# wavplayer-v2.net
KiCad netlist of a schematic drawn in EAGLE
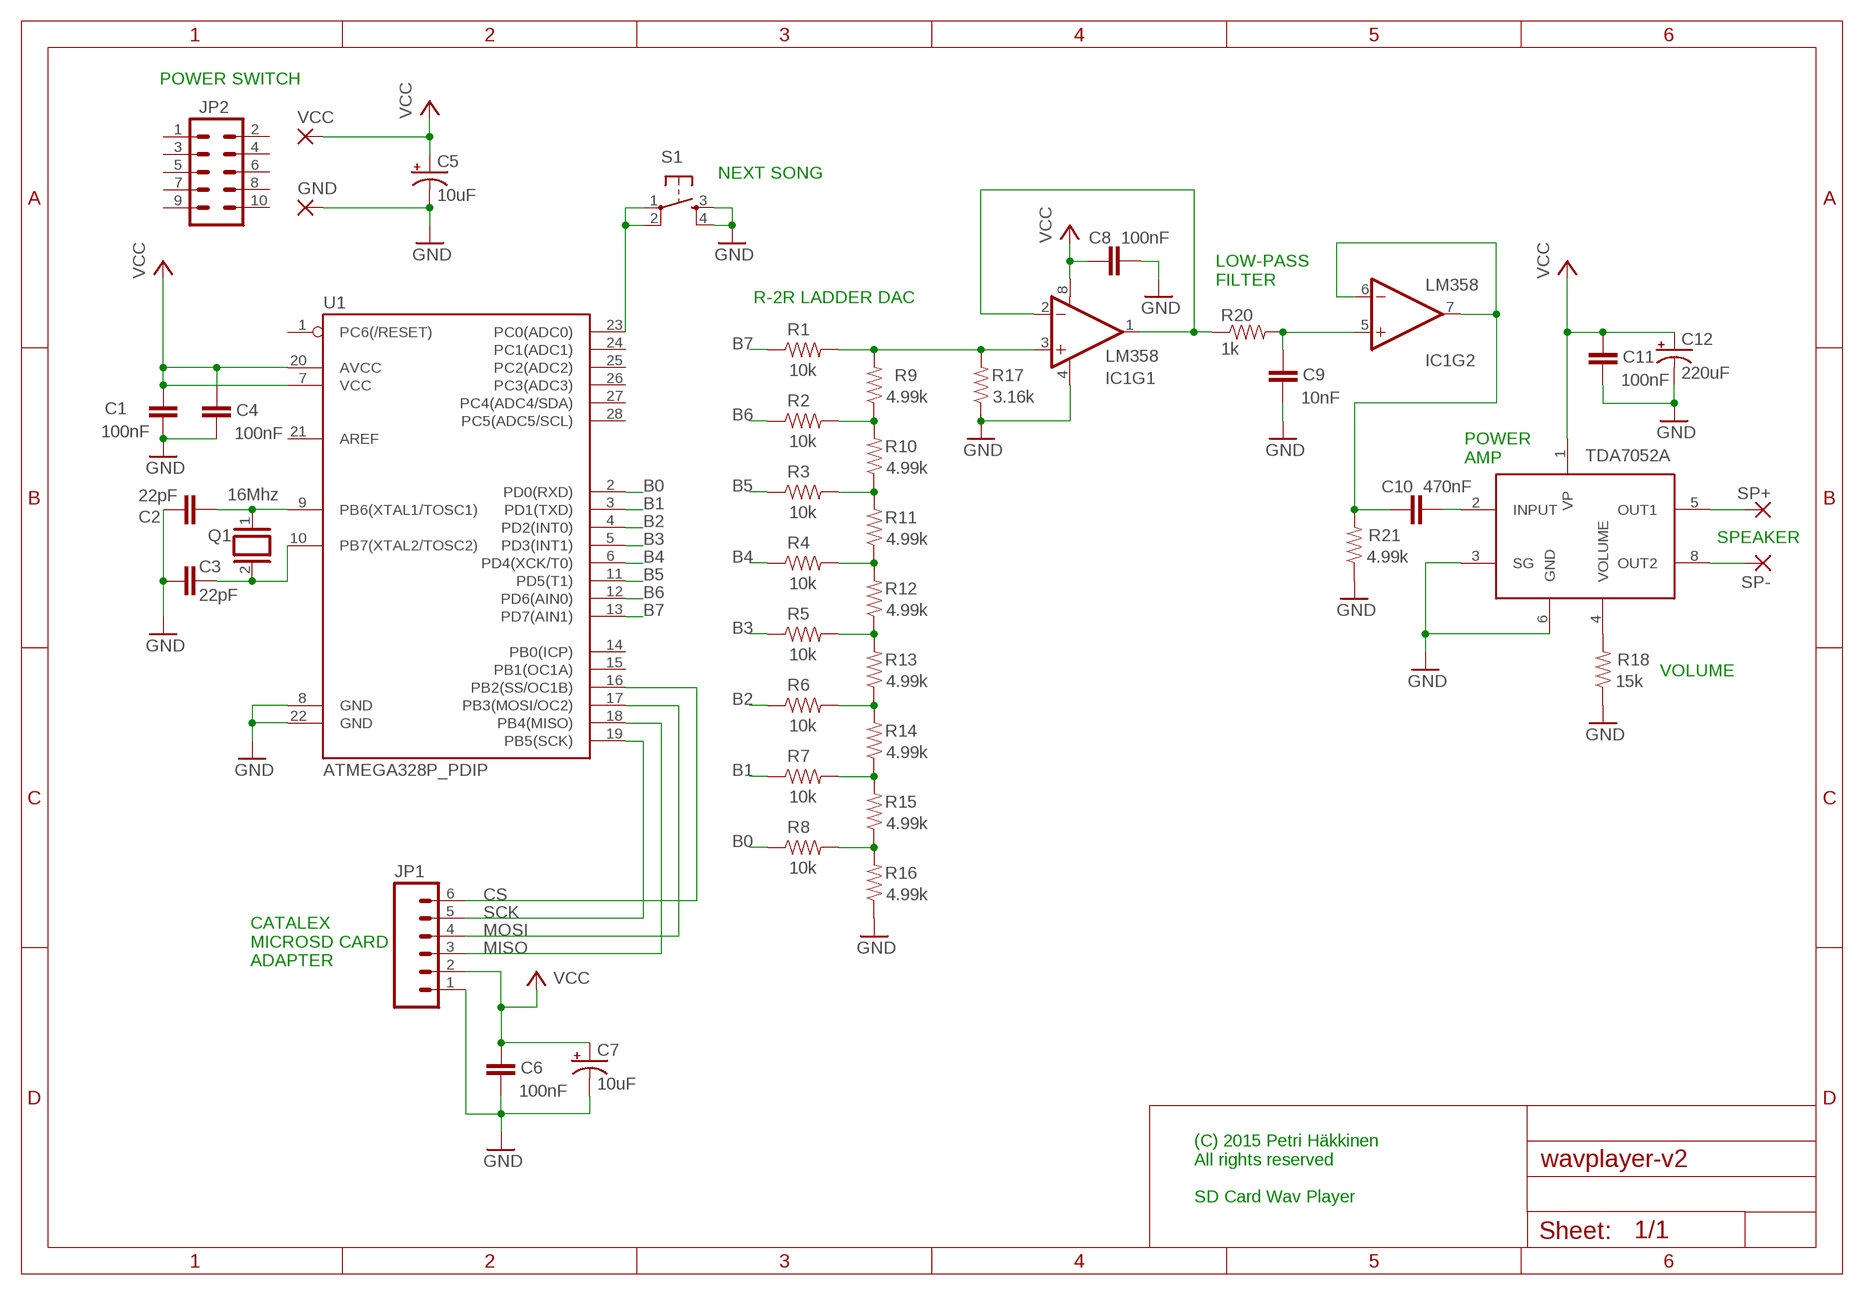
[diagram p0: schematic, sheet 1]

(export (version "E")
  (design (tool "Eeschema 10.0.6"))
  (components
    (comp (ref "C1")
      (value "100nF")
      (footprint "eagle-import:CAP-PTH-SMALL")
      (libsource (lib "eagle-import") (part "CAPPTH"))
    )
    (comp (ref "C2")
      (value "22pF")
      (footprint "eagle-import:CAP-PTH-SMALL")
      (libsource (lib "eagle-import") (part "CAPPTH"))
    )
    (comp (ref "C3")
      (value "22pF")
      (footprint "eagle-import:CAP-PTH-SMALL")
      (libsource (lib "eagle-import") (part "CAPPTH"))
    )
    (comp (ref "C4")
      (value "100nF")
      (footprint "eagle-import:CAP-PTH-SMALL")
      (libsource (lib "eagle-import") (part "CAPPTH"))
    )
    (comp (ref "C5")
      (value "10uF")
      (footprint "eagle-import:CPOL-RADIAL-100UF-25V")
      (libsource (lib "eagle-import") (part "CAP_POLPTH1"))
    )
    (comp (ref "C6")
      (value "100nF")
      (footprint "eagle-import:CAP-PTH-SMALL")
      (libsource (lib "eagle-import") (part "CAPPTH"))
    )
    (comp (ref "C7")
      (value "10uF")
      (footprint "eagle-import:CPOL-RADIAL-100UF-25V")
      (libsource (lib "eagle-import") (part "CAP_POLPTH1"))
    )
    (comp (ref "C8")
      (value "100nF")
      (footprint "eagle-import:CAP-PTH-SMALL")
      (libsource (lib "eagle-import") (part "CAPPTH"))
    )
    (comp (ref "C9")
      (value "10nF")
      (footprint "eagle-import:CAP-PTH-SMALL")
      (libsource (lib "eagle-import") (part "CAPPTH"))
    )
    (comp (ref "C10")
      (value "470nF")
      (footprint "eagle-import:CAP-PTH-SMALL")
      (libsource (lib "eagle-import") (part "CAPPTH"))
    )
    (comp (ref "C11")
      (value "100nF")
      (footprint "eagle-import:CAP-PTH-SMALL")
      (libsource (lib "eagle-import") (part "CAPPTH"))
    )
    (comp (ref "C12")
      (value "220uF")
      (footprint "eagle-import:CPOL-RADIAL-100UF-25V")
      (libsource (lib "eagle-import") (part "CAP_POLPTH1"))
    )
    (comp (ref "GND")
      (value "WIREPAD2,54/0,8")
      (footprint "eagle-import:2,54_0,8")
      (libsource (lib "eagle-import") (part "WIREPAD2,54/0,8"))
    )
    (comp (ref "IC1")
      (value "LM358")
      (footprint "eagle-import:DIP08")
      (libsource (lib "eagle-import") (part "LM358"))
    )
    (comp (ref "JP1")
      (value "M06LONGPADS")
      (footprint "eagle-import:1X06_LONGPADS")
      (libsource (lib "eagle-import") (part "M06LONGPADS"))
    )
    (comp (ref "JP2")
      (value "M05X2NO_SILK")
      (footprint "eagle-import:2X5_NOSILK")
      (libsource (lib "eagle-import") (part "M05X2NO_SILK"))
    )
    (comp (ref "Q1")
      (value "16Mhz")
      (footprint "eagle-import:QS")
      (libsource (lib "eagle-import") (part "XTAL/S"))
    )
    (comp (ref "R1")
      (value "10k")
      (footprint "eagle-import:AXIAL-0.4")
      (libsource (lib "eagle-import") (part "RESISTORPTH-1/4W"))
    )
    (comp (ref "R2")
      (value "10k")
      (footprint "eagle-import:AXIAL-0.4")
      (libsource (lib "eagle-import") (part "RESISTORPTH-1/4W"))
    )
    (comp (ref "R3")
      (value "10k")
      (footprint "eagle-import:AXIAL-0.4")
      (libsource (lib "eagle-import") (part "RESISTORPTH-1/4W"))
    )
    (comp (ref "R4")
      (value "10k")
      (footprint "eagle-import:AXIAL-0.4")
      (libsource (lib "eagle-import") (part "RESISTORPTH-1/4W"))
    )
    (comp (ref "R5")
      (value "10k")
      (footprint "eagle-import:AXIAL-0.4")
      (libsource (lib "eagle-import") (part "RESISTORPTH-1/4W"))
    )
    (comp (ref "R6")
      (value "10k")
      (footprint "eagle-import:AXIAL-0.4")
      (libsource (lib "eagle-import") (part "RESISTORPTH-1/4W"))
    )
    (comp (ref "R7")
      (value "10k")
      (footprint "eagle-import:AXIAL-0.4")
      (libsource (lib "eagle-import") (part "RESISTORPTH-1/4W"))
    )
    (comp (ref "R8")
      (value "10k")
      (footprint "eagle-import:AXIAL-0.4")
      (libsource (lib "eagle-import") (part "RESISTORPTH-1/4W"))
    )
    (comp (ref "R9")
      (value "4.99k")
      (footprint "eagle-import:AXIAL-0.4")
      (libsource (lib "eagle-import") (part "RESISTORPTH-1/4W"))
    )
    (comp (ref "R10")
      (value "4.99k")
      (footprint "eagle-import:AXIAL-0.4")
      (libsource (lib "eagle-import") (part "RESISTORPTH-1/4W"))
    )
    (comp (ref "R11")
      (value "4.99k")
      (footprint "eagle-import:AXIAL-0.4")
      (libsource (lib "eagle-import") (part "RESISTORPTH-1/4W"))
    )
    (comp (ref "R12")
      (value "4.99k")
      (footprint "eagle-import:AXIAL-0.4")
      (libsource (lib "eagle-import") (part "RESISTORPTH-1/4W"))
    )
    (comp (ref "R13")
      (value "4.99k")
      (footprint "eagle-import:AXIAL-0.4")
      (libsource (lib "eagle-import") (part "RESISTORPTH-1/4W"))
    )
    (comp (ref "R14")
      (value "4.99k")
      (footprint "eagle-import:AXIAL-0.4")
      (libsource (lib "eagle-import") (part "RESISTORPTH-1/4W"))
    )
    (comp (ref "R15")
      (value "4.99k")
      (footprint "eagle-import:AXIAL-0.4")
      (libsource (lib "eagle-import") (part "RESISTORPTH-1/4W"))
    )
    (comp (ref "R16")
      (value "4.99k")
      (footprint "eagle-import:AXIAL-0.4")
      (libsource (lib "eagle-import") (part "RESISTORPTH-1/4W"))
    )
    (comp (ref "R17")
      (value "3.16k")
      (footprint "eagle-import:AXIAL-0.4")
      (libsource (lib "eagle-import") (part "RESISTORPTH-1/4W"))
    )
    (comp (ref "R18")
      (value "15k")
      (footprint "eagle-import:AXIAL-0.1")
      (libsource (lib "eagle-import") (part "RESISTORPTH-1/4W-VERT"))
    )
    (comp (ref "R20")
      (value "1k")
      (footprint "eagle-import:AXIAL-0.4")
      (libsource (lib "eagle-import") (part "RESISTORPTH-1/4W"))
    )
    (comp (ref "R21")
      (value "4.99k")
      (footprint "eagle-import:AXIAL-0.4")
      (libsource (lib "eagle-import") (part "RESISTORPTH-1/4W"))
    )
    (comp (ref "S1")
      (value "TAC_SWITCHPTH")
      (footprint "eagle-import:TACTILE-PTH")
      (libsource (lib "eagle-import") (part "TAC_SWITCHPTH"))
    )
    (comp (ref "SP+")
      (value "WIREPAD3,17/1,1")
      (footprint "eagle-import:3,17_1,1")
      (libsource (lib "eagle-import") (part "WIREPAD3,17/1,1"))
    )
    (comp (ref "SP-")
      (value "WIREPAD3,17/1,1")
      (footprint "eagle-import:3,17_1,1")
      (libsource (lib "eagle-import") (part "WIREPAD3,17/1,1"))
    )
    (comp (ref "U$1")
      (value "TDA7052B")
      (footprint "eagle-import:DIL08")
      (libsource (lib "eagle-import") (part "TDA7052B"))
    )
    (comp (ref "U1")
      (value "ATMEGA328P_PDIP")
      (footprint "eagle-import:DIL28-3")
      (libsource (lib "eagle-import") (part "ATMEGA328P_PDIP"))
    )
    (comp (ref "VCC")
      (value "WIREPAD2,54/0,8")
      (footprint "eagle-import:2,54_0,8")
      (libsource (lib "eagle-import") (part "WIREPAD2,54/0,8"))
    )
  )
  (nets
    (net (code "1") (name "/B0") (class "Default")
      (node (ref "R8") (pin "P$1") (pinfunction "1_P$1") (pintype "passive"))
      (node (ref "U1") (pin "2") (pinfunction "PD0(RXD)_2") (pintype "bidirectional"))
    )
    (net (code "2") (name "/B1") (class "Default")
      (node (ref "R7") (pin "P$1") (pinfunction "1_P$1") (pintype "passive"))
      (node (ref "U1") (pin "3") (pinfunction "PD1(TXD)_3") (pintype "bidirectional"))
    )
    (net (code "3") (name "/B2") (class "Default")
      (node (ref "R6") (pin "P$1") (pinfunction "1_P$1") (pintype "passive"))
      (node (ref "U1") (pin "4") (pinfunction "PD2(INT0)_4") (pintype "bidirectional"))
    )
    (net (code "4") (name "/B3") (class "Default")
      (node (ref "R5") (pin "P$1") (pinfunction "1_P$1") (pintype "passive"))
      (node (ref "U1") (pin "5") (pinfunction "PD3(INT1)_5") (pintype "bidirectional"))
    )
    (net (code "5") (name "/B4") (class "Default")
      (node (ref "R4") (pin "P$1") (pinfunction "1_P$1") (pintype "passive"))
      (node (ref "U1") (pin "6") (pinfunction "PD4(XCK/T0)_6") (pintype "bidirectional"))
    )
    (net (code "6") (name "/B5") (class "Default")
      (node (ref "R3") (pin "P$1") (pinfunction "1_P$1") (pintype "passive"))
      (node (ref "U1") (pin "11") (pinfunction "PD5(T1)_11") (pintype "bidirectional"))
    )
    (net (code "7") (name "/B6") (class "Default")
      (node (ref "R2") (pin "P$1") (pinfunction "1_P$1") (pintype "passive"))
      (node (ref "U1") (pin "12") (pinfunction "PD6(AIN0)_12") (pintype "bidirectional"))
    )
    (net (code "8") (name "/B7") (class "Default")
      (node (ref "R1") (pin "P$1") (pinfunction "1_P$1") (pintype "passive"))
      (node (ref "U1") (pin "13") (pinfunction "PD7(AIN1)_13") (pintype "bidirectional"))
    )
    (net (code "9") (name "/CS") (class "Default")
      (node (ref "JP1") (pin "6") (pinfunction "6_6") (pintype "passive"))
      (node (ref "U1") (pin "16") (pinfunction "PB2(SS/OC1B)_16") (pintype "bidirectional"))
    )
    (net (code "10") (name "/MISO") (class "Default")
      (node (ref "JP1") (pin "3") (pinfunction "3_3") (pintype "passive"))
      (node (ref "U1") (pin "18") (pinfunction "PB4(MISO)_18") (pintype "bidirectional"))
    )
    (net (code "11") (name "/MOSI") (class "Default")
      (node (ref "JP1") (pin "4") (pinfunction "4_4") (pintype "passive"))
      (node (ref "U1") (pin "17") (pinfunction "PB3(MOSI/OC2)_17") (pintype "bidirectional"))
    )
    (net (code "12") (name "/SCK") (class "Default")
      (node (ref "JP1") (pin "5") (pinfunction "5_5") (pintype "passive"))
      (node (ref "U1") (pin "19") (pinfunction "PB5(SCK)_19") (pintype "bidirectional"))
    )
    (net (code "13") (name "GND") (class "Default")
      (node (ref "C1") (pin "2") (pinfunction "2_2") (pintype "passive"))
      (node (ref "C11") (pin "2") (pinfunction "2_2") (pintype "passive"))
      (node (ref "C12") (pin "2") (pinfunction "-_2") (pintype "passive"))
      (node (ref "C2") (pin "2") (pinfunction "2_2") (pintype "passive"))
      (node (ref "C3") (pin "2") (pinfunction "2_2") (pintype "passive"))
      (node (ref "C4") (pin "2") (pinfunction "2_2") (pintype "passive"))
      (node (ref "C5") (pin "2") (pinfunction "-_2") (pintype "passive"))
      (node (ref "C6") (pin "2") (pinfunction "2_2") (pintype "passive"))
      (node (ref "C7") (pin "2") (pinfunction "-_2") (pintype "passive"))
      (node (ref "C8") (pin "2") (pinfunction "2_2") (pintype "passive"))
      (node (ref "C9") (pin "2") (pinfunction "2_2") (pintype "passive"))
      (node (ref "GND") (pin "1") (pinfunction "P_1") (pintype "passive"))
      (node (ref "IC1") (pin "4") (pinfunction "V-_4") (pintype "power_in"))
      (node (ref "JP1") (pin "1") (pinfunction "1_1") (pintype "passive"))
      (node (ref "R16") (pin "P$1") (pinfunction "1_P$1") (pintype "passive"))
      (node (ref "R17") (pin "P$1") (pinfunction "1_P$1") (pintype "passive"))
      (node (ref "R18") (pin "P$1") (pinfunction "1_P$1") (pintype "passive"))
      (node (ref "R21") (pin "P$1") (pinfunction "1_P$1") (pintype "passive"))
      (node (ref "S1") (pin "3") (pinfunction "3_3") (pintype "passive"))
      (node (ref "S1") (pin "4") (pinfunction "4_4") (pintype "passive"))
      (node (ref "U$1") (pin "3") (pinfunction "SG_3") (pintype "power_in"))
      (node (ref "U$1") (pin "6") (pinfunction "GND_6") (pintype "power_in"))
      (node (ref "U1") (pin "22") (pinfunction "GND_22") (pintype "bidirectional"))
      (node (ref "U1") (pin "8") (pinfunction "GND_8") (pintype "bidirectional"))
    )
    (net (code "14") (name "Net-(IC1A-+IN)") (class "Default")
      (node (ref "IC1") (pin "3") (pinfunction "+IN_3") (pintype "input"))
      (node (ref "R1") (pin "P$2") (pinfunction "2_P$2") (pintype "passive"))
      (node (ref "R17") (pin "P$2") (pinfunction "2_P$2") (pintype "passive"))
      (node (ref "R9") (pin "P$2") (pinfunction "2_P$2") (pintype "passive"))
    )
    (net (code "15") (name "Net-(IC1A--IN)") (class "Default")
      (node (ref "IC1") (pin "1") (pinfunction "OUT_1") (pintype "output"))
      (node (ref "IC1") (pin "2") (pinfunction "-IN_2") (pintype "input"))
      (node (ref "R20") (pin "P$1") (pinfunction "1_P$1") (pintype "passive"))
    )
    (net (code "16") (name "Net-(IC1B-+IN)") (class "Default")
      (node (ref "C9") (pin "1") (pinfunction "1_1") (pintype "passive"))
      (node (ref "IC1") (pin "5") (pinfunction "+IN_5") (pintype "input"))
      (node (ref "R20") (pin "P$2") (pinfunction "2_P$2") (pintype "passive"))
    )
    (net (code "17") (name "Net-(IC1B--IN)") (class "Default")
      (node (ref "C10") (pin "1") (pinfunction "1_1") (pintype "passive"))
      (node (ref "IC1") (pin "6") (pinfunction "-IN_6") (pintype "input"))
      (node (ref "IC1") (pin "7") (pinfunction "OUT_7") (pintype "output"))
      (node (ref "R21") (pin "P$2") (pinfunction "2_P$2") (pintype "passive"))
    )
    (net (code "18") (name "Net-(R10-1)") (class "Default")
      (node (ref "R10") (pin "P$1") (pinfunction "1_P$1") (pintype "passive"))
      (node (ref "R11") (pin "P$2") (pinfunction "2_P$2") (pintype "passive"))
      (node (ref "R3") (pin "P$2") (pinfunction "2_P$2") (pintype "passive"))
    )
    (net (code "19") (name "Net-(R10-2)") (class "Default")
      (node (ref "R10") (pin "P$2") (pinfunction "2_P$2") (pintype "passive"))
      (node (ref "R2") (pin "P$2") (pinfunction "2_P$2") (pintype "passive"))
      (node (ref "R9") (pin "P$1") (pinfunction "1_P$1") (pintype "passive"))
    )
    (net (code "20") (name "Net-(R11-1)") (class "Default")
      (node (ref "R11") (pin "P$1") (pinfunction "1_P$1") (pintype "passive"))
      (node (ref "R12") (pin "P$2") (pinfunction "2_P$2") (pintype "passive"))
      (node (ref "R4") (pin "P$2") (pinfunction "2_P$2") (pintype "passive"))
    )
    (net (code "21") (name "Net-(R12-1)") (class "Default")
      (node (ref "R12") (pin "P$1") (pinfunction "1_P$1") (pintype "passive"))
      (node (ref "R13") (pin "P$2") (pinfunction "2_P$2") (pintype "passive"))
      (node (ref "R5") (pin "P$2") (pinfunction "2_P$2") (pintype "passive"))
    )
    (net (code "22") (name "Net-(R13-1)") (class "Default")
      (node (ref "R13") (pin "P$1") (pinfunction "1_P$1") (pintype "passive"))
      (node (ref "R14") (pin "P$2") (pinfunction "2_P$2") (pintype "passive"))
      (node (ref "R6") (pin "P$2") (pinfunction "2_P$2") (pintype "passive"))
    )
    (net (code "23") (name "Net-(R14-1)") (class "Default")
      (node (ref "R14") (pin "P$1") (pinfunction "1_P$1") (pintype "passive"))
      (node (ref "R15") (pin "P$2") (pinfunction "2_P$2") (pintype "passive"))
      (node (ref "R7") (pin "P$2") (pinfunction "2_P$2") (pintype "passive"))
    )
    (net (code "24") (name "Net-(R15-1)") (class "Default")
      (node (ref "R15") (pin "P$1") (pinfunction "1_P$1") (pintype "passive"))
      (node (ref "R16") (pin "P$2") (pinfunction "2_P$2") (pintype "passive"))
      (node (ref "R8") (pin "P$2") (pinfunction "2_P$2") (pintype "passive"))
    )
    (net (code "25") (name "Net-(R18-2)") (class "Default")
      (node (ref "R18") (pin "P$2") (pinfunction "2_P$2") (pintype "passive"))
      (node (ref "U$1") (pin "4") (pinfunction "VOLUME_4") (pintype "power_in"))
    )
    (net (code "26") (name "Net-(SP+-P)") (class "Default")
      (node (ref "SP+") (pin "1") (pinfunction "P_1") (pintype "passive"))
      (node (ref "U$1") (pin "5") (pinfunction "OUT1_5") (pintype "output"))
    )
    (net (code "27") (name "Net-(SP--P)") (class "Default")
      (node (ref "SP-") (pin "1") (pinfunction "P_1") (pintype "passive"))
      (node (ref "U$1") (pin "8") (pinfunction "OUT2_8") (pintype "output"))
    )
    (net (code "28") (name "Net-(U$1-INPUT)") (class "Default")
      (node (ref "C10") (pin "2") (pinfunction "2_2") (pintype "passive"))
      (node (ref "U$1") (pin "2") (pinfunction "INPUT_2") (pintype "input"))
    )
    (net (code "29") (name "Net-(U1-PB6(XTAL1{slash}TOSC1))") (class "Default")
      (node (ref "C2") (pin "1") (pinfunction "1_1") (pintype "passive"))
      (node (ref "Q1") (pin "1") (pinfunction "1_1") (pintype "passive"))
      (node (ref "U1") (pin "9") (pinfunction "PB6(XTAL1/TOSC1)_9") (pintype "bidirectional"))
    )
    (net (code "30") (name "Net-(U1-PB7(XTAL2{slash}TOSC2))") (class "Default")
      (node (ref "C3") (pin "1") (pinfunction "1_1") (pintype "passive"))
      (node (ref "Q1") (pin "2") (pinfunction "2_2") (pintype "passive"))
      (node (ref "U1") (pin "10") (pinfunction "PB7(XTAL2/TOSC2)_10") (pintype "bidirectional"))
    )
    (net (code "31") (name "Net-(U1-PC0(ADC0))") (class "Default")
      (node (ref "S1") (pin "1") (pinfunction "1_1") (pintype "passive"))
      (node (ref "S1") (pin "2") (pinfunction "2_2") (pintype "passive"))
      (node (ref "U1") (pin "23") (pinfunction "PC0(ADC0)_23") (pintype "bidirectional"))
    )
    (net (code "32") (name "VCC") (class "Default")
      (node (ref "C1") (pin "1") (pinfunction "1_1") (pintype "passive"))
      (node (ref "C11") (pin "1") (pinfunction "1_1") (pintype "passive"))
      (node (ref "C12") (pin "1") (pinfunction "+_1") (pintype "passive"))
      (node (ref "C4") (pin "1") (pinfunction "1_1") (pintype "passive"))
      (node (ref "C5") (pin "1") (pinfunction "+_1") (pintype "passive"))
      (node (ref "C6") (pin "1") (pinfunction "1_1") (pintype "passive"))
      (node (ref "C7") (pin "1") (pinfunction "+_1") (pintype "passive"))
      (node (ref "C8") (pin "1") (pinfunction "1_1") (pintype "passive"))
      (node (ref "IC1") (pin "8") (pinfunction "V+_8") (pintype "power_in"))
      (node (ref "JP1") (pin "2") (pinfunction "2_2") (pintype "passive"))
      (node (ref "U$1") (pin "1") (pinfunction "VP_1") (pintype "power_in"))
      (node (ref "U1") (pin "20") (pinfunction "AVCC_20") (pintype "bidirectional"))
      (node (ref "U1") (pin "7") (pinfunction "VCC_7") (pintype "bidirectional"))
      (node (ref "VCC") (pin "1") (pinfunction "P_1") (pintype "passive"))
    )
    (net (code "33") (name "unconnected-(JP2-Pad1)") (class "Default")
      (node (ref "JP2") (pin "1") (pinfunction "1_1") (pintype "passive"))
    )
    (net (code "34") (name "unconnected-(JP2-Pad2)") (class "Default")
      (node (ref "JP2") (pin "2") (pinfunction "2_2") (pintype "passive"))
    )
    (net (code "35") (name "unconnected-(JP2-Pad3)") (class "Default")
      (node (ref "JP2") (pin "3") (pinfunction "3_3") (pintype "passive"))
    )
    (net (code "36") (name "unconnected-(JP2-Pad4)") (class "Default")
      (node (ref "JP2") (pin "4") (pinfunction "4_4") (pintype "passive"))
    )
    (net (code "37") (name "unconnected-(JP2-Pad5)") (class "Default")
      (node (ref "JP2") (pin "5") (pinfunction "5_5") (pintype "passive"))
    )
    (net (code "38") (name "unconnected-(JP2-Pad6)") (class "Default")
      (node (ref "JP2") (pin "6") (pinfunction "6_6") (pintype "passive"))
    )
    (net (code "39") (name "unconnected-(JP2-Pad7)") (class "Default")
      (node (ref "JP2") (pin "7") (pinfunction "7_7") (pintype "passive"))
    )
    (net (code "40") (name "unconnected-(JP2-Pad8)") (class "Default")
      (node (ref "JP2") (pin "8") (pinfunction "8_8") (pintype "passive"))
    )
    (net (code "41") (name "unconnected-(JP2-Pad9)") (class "Default")
      (node (ref "JP2") (pin "9") (pinfunction "9_9") (pintype "passive"))
    )
    (net (code "42") (name "unconnected-(JP2-Pad10)") (class "Default")
      (node (ref "JP2") (pin "10") (pinfunction "10_10") (pintype "passive"))
    )
    (net (code "43") (name "unconnected-(U1-AREF-Pad21)") (class "Default")
      (node (ref "U1") (pin "21") (pinfunction "AREF_21") (pintype "bidirectional"))
    )
    (net (code "44") (name "unconnected-(U1-PB0(ICP)-Pad14)") (class "Default")
      (node (ref "U1") (pin "14") (pinfunction "PB0(ICP)_14") (pintype "bidirectional"))
    )
    (net (code "45") (name "unconnected-(U1-PB1(OC1A)-Pad15)") (class "Default")
      (node (ref "U1") (pin "15") (pinfunction "PB1(OC1A)_15") (pintype "bidirectional"))
    )
    (net (code "46") (name "unconnected-(U1-PC1(ADC1)-Pad24)") (class "Default")
      (node (ref "U1") (pin "24") (pinfunction "PC1(ADC1)_24") (pintype "bidirectional"))
    )
    (net (code "47") (name "unconnected-(U1-PC2(ADC2)-Pad25)") (class "Default")
      (node (ref "U1") (pin "25") (pinfunction "PC2(ADC2)_25") (pintype "bidirectional"))
    )
    (net (code "48") (name "unconnected-(U1-PC3(ADC3)-Pad26)") (class "Default")
      (node (ref "U1") (pin "26") (pinfunction "PC3(ADC3)_26") (pintype "bidirectional"))
    )
    (net (code "49") (name "unconnected-(U1-PC4(ADC4{slash}SDA)-Pad27)") (class "Default")
      (node (ref "U1") (pin "27") (pinfunction "PC4(ADC4/SDA)_27") (pintype "bidirectional"))
    )
    (net (code "50") (name "unconnected-(U1-PC5(ADC5{slash}SCL)-Pad28)") (class "Default")
      (node (ref "U1") (pin "28") (pinfunction "PC5(ADC5/SCL)_28") (pintype "bidirectional"))
    )
    (net (code "51") (name "unconnected-(U1-PC6({slash}RESET)-Pad1)") (class "Default")
      (node (ref "U1") (pin "1") (pinfunction "PC6(/RESET)_1") (pintype "bidirectional"))
    )
  )
)
